# Power_REF_2V5.net
KiCad netlist of a schematic drawn in Altium Designer
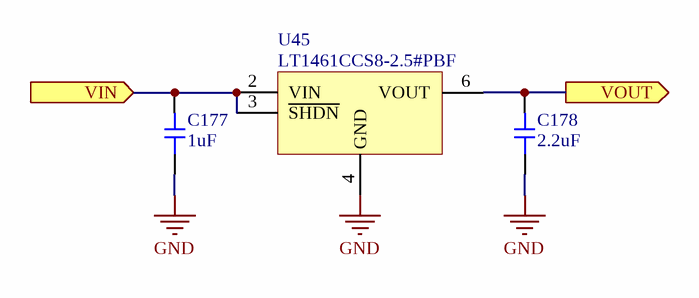
[diagram p0: Power_REF_2V5.SchDoc]

(export (version "E")
  (design (tool "Eeschema 10.0.6"))
  (components
    (comp (ref "C177")
      (value "1uF")
      (footprint "0603-CAP")
      (description "Capacitor")
      (fields
        (field (name "MANUFACTURER") "Samsung")
        (field (name "MANUFACTURER PART NUMBER") "CL10B105MO8NNWC")
      )
      (libsource (lib "AMDC") (part "Capacitor"))
    )
    (comp (ref "C178")
      (value "2.2uF")
      (footprint "0603-CAP")
      (description "Capacitor")
      (fields
        (field (name "MANUFACTURER") "Murata")
        (field (name "MANUFACTURER PART NUMBER") "GRM188R6YA225MA12D")
      )
      (libsource (lib "AMDC") (part "Capacitor"))
    )
    (comp (ref "U45")
      (value "LT1461CCS8-2.5#PBF")
      (footprint "SOIC8_N")
      (description "IC VREF SERIES 2.5V 8SOIC")
      (fields
        (field (name "MANUFACTURER") "Analog Devices / Linear Technology")
        (field (name "TOLERANCE") "0.08%")
      )
      (libsource (lib "AMDC") (part "LT1461CCS8-2.5#PBF"))
    )
  )
  (nets
    (net (code "1") (name "/VIN") (class "Default")
      (node (ref "C177") (pin "1") (pinfunction "1_1") (pintype "passive"))
      (node (ref "U45") (pin "2") (pinfunction "VIN_2") (pintype "passive"))
      (node (ref "U45") (pin "3") (pinfunction "~{SHDN}_3") (pintype "passive"))
    )
    (net (code "2") (name "/VOUT") (class "Default")
      (node (ref "C178") (pin "1") (pinfunction "1_1") (pintype "passive"))
      (node (ref "U45") (pin "6") (pinfunction "VOUT_6") (pintype "passive"))
    )
    (net (code "3") (name "GND") (class "Default")
      (node (ref "C177") (pin "2") (pinfunction "2_2") (pintype "passive"))
      (node (ref "C178") (pin "2") (pinfunction "2_2") (pintype "passive"))
      (node (ref "U45") (pin "4") (pinfunction "GND_4") (pintype "passive"))
    )
  )
)
